# untitled.net
KiCad netlist of a schematic drawn in EAGLE
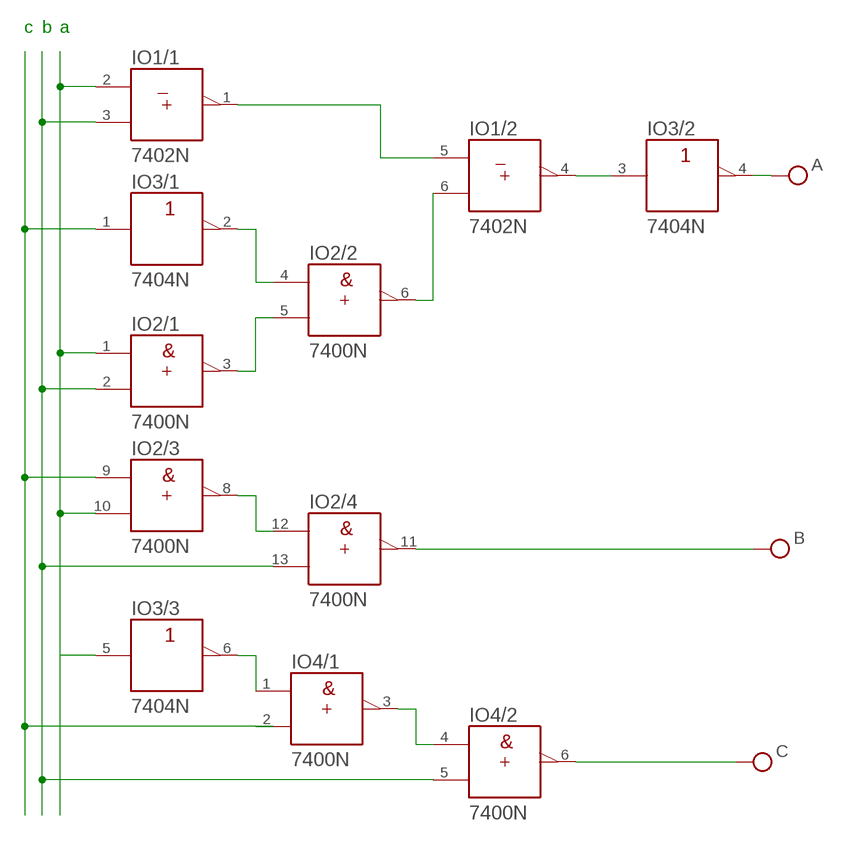
[diagram p0: schematic, sheet 1]

(export (version "E")
  (design (tool "Eeschema 10.0.6"))
  (components
    (comp (ref "IO1")
      (value "7402N")
      (footprint "eagle-import:DIL14")
      (libsource (lib "eagle-import") (part "7402N"))
    )
    (comp (ref "IO2")
      (value "7400N")
      (footprint "eagle-import:DIL14")
      (libsource (lib "eagle-import") (part "7400N"))
    )
    (comp (ref "IO3")
      (value "7404N")
      (footprint "eagle-import:DIL14")
      (libsource (lib "eagle-import") (part "7404N"))
    )
    (comp (ref "IO4")
      (value "7400N")
      (footprint "eagle-import:DIL14")
      (libsource (lib "eagle-import") (part "7400N"))
    )
  )
  (nets
    (net (code "1") (name "/N$1") (class "Default")
      (node (ref "IO1") (pin "2") (pinfunction "A_2") (pintype "input"))
      (node (ref "IO1") (pin "3") (pinfunction "B_3") (pintype "input"))
      (node (ref "IO2") (pin "1") (pinfunction "A_1") (pintype "input"))
      (node (ref "IO2") (pin "10") (pinfunction "B_10") (pintype "input"))
      (node (ref "IO2") (pin "13") (pinfunction "B_13") (pintype "input"))
      (node (ref "IO2") (pin "2") (pinfunction "B_2") (pintype "input"))
      (node (ref "IO2") (pin "9") (pinfunction "A_9") (pintype "input"))
      (node (ref "IO3") (pin "1") (pinfunction "A_1") (pintype "input"))
      (node (ref "IO3") (pin "5") (pinfunction "A_5") (pintype "input"))
      (node (ref "IO4") (pin "5") (pinfunction "B_5") (pintype "input"))
    )
    (net (code "2") (name "A") (class "Default")
      (node (ref "IO2") (pin "11") (pinfunction "Y_11") (pintype "output"))
      (node (ref "IO3") (pin "4") (pinfunction "Y_4") (pintype "output"))
      (node (ref "IO4") (pin "6") (pinfunction "Y_6") (pintype "output"))
    )
    (net (code "3") (name "Net-(IO1C-Y)") (class "Default")
      (node (ref "IO1") (pin "1") (pinfunction "Y_1") (pintype "output"))
      (node (ref "IO1") (pin "5") (pinfunction "A_5") (pintype "input"))
    )
    (net (code "4") (name "Net-(IO1D-B)") (class "Default")
      (node (ref "IO1") (pin "6") (pinfunction "B_6") (pintype "input"))
      (node (ref "IO2") (pin "6") (pinfunction "Y_6") (pintype "output"))
    )
    (net (code "5") (name "Net-(IO1D-Y)") (class "Default")
      (node (ref "IO1") (pin "4") (pinfunction "Y_4") (pintype "output"))
      (node (ref "IO3") (pin "3") (pinfunction "A_3") (pintype "input"))
    )
    (net (code "6") (name "Net-(IO2C-Y)") (class "Default")
      (node (ref "IO2") (pin "3") (pinfunction "Y_3") (pintype "output"))
      (node (ref "IO2") (pin "5") (pinfunction "B_5") (pintype "input"))
    )
    (net (code "7") (name "Net-(IO2D-A)") (class "Default")
      (node (ref "IO2") (pin "4") (pinfunction "A_4") (pintype "input"))
      (node (ref "IO3") (pin "2") (pinfunction "Y_2") (pintype "output"))
    )
    (net (code "8") (name "Net-(IO2E-Y)") (class "Default")
      (node (ref "IO2") (pin "12") (pinfunction "A_12") (pintype "input"))
      (node (ref "IO2") (pin "8") (pinfunction "Y_8") (pintype "output"))
    )
    (net (code "9") (name "Net-(IO3E-Y)") (class "Default")
      (node (ref "IO3") (pin "6") (pinfunction "Y_6") (pintype "output"))
      (node (ref "IO4") (pin "1") (pinfunction "A_1") (pintype "input"))
    )
    (net (code "10") (name "Net-(IO4C-Y)") (class "Default")
      (node (ref "IO4") (pin "3") (pinfunction "Y_3") (pintype "output"))
      (node (ref "IO4") (pin "4") (pinfunction "A_4") (pintype "input"))
    )
    (net (code "11") (name "unconnected-(IO4C-B-Pad2)") (class "Default")
      (node (ref "IO4") (pin "2") (pinfunction "B_2") (pintype "input"))
    )
  )
)
